# SCH_Manta_2023-12-03.net
KiCad netlist of a schematic drawn in EasyEDA
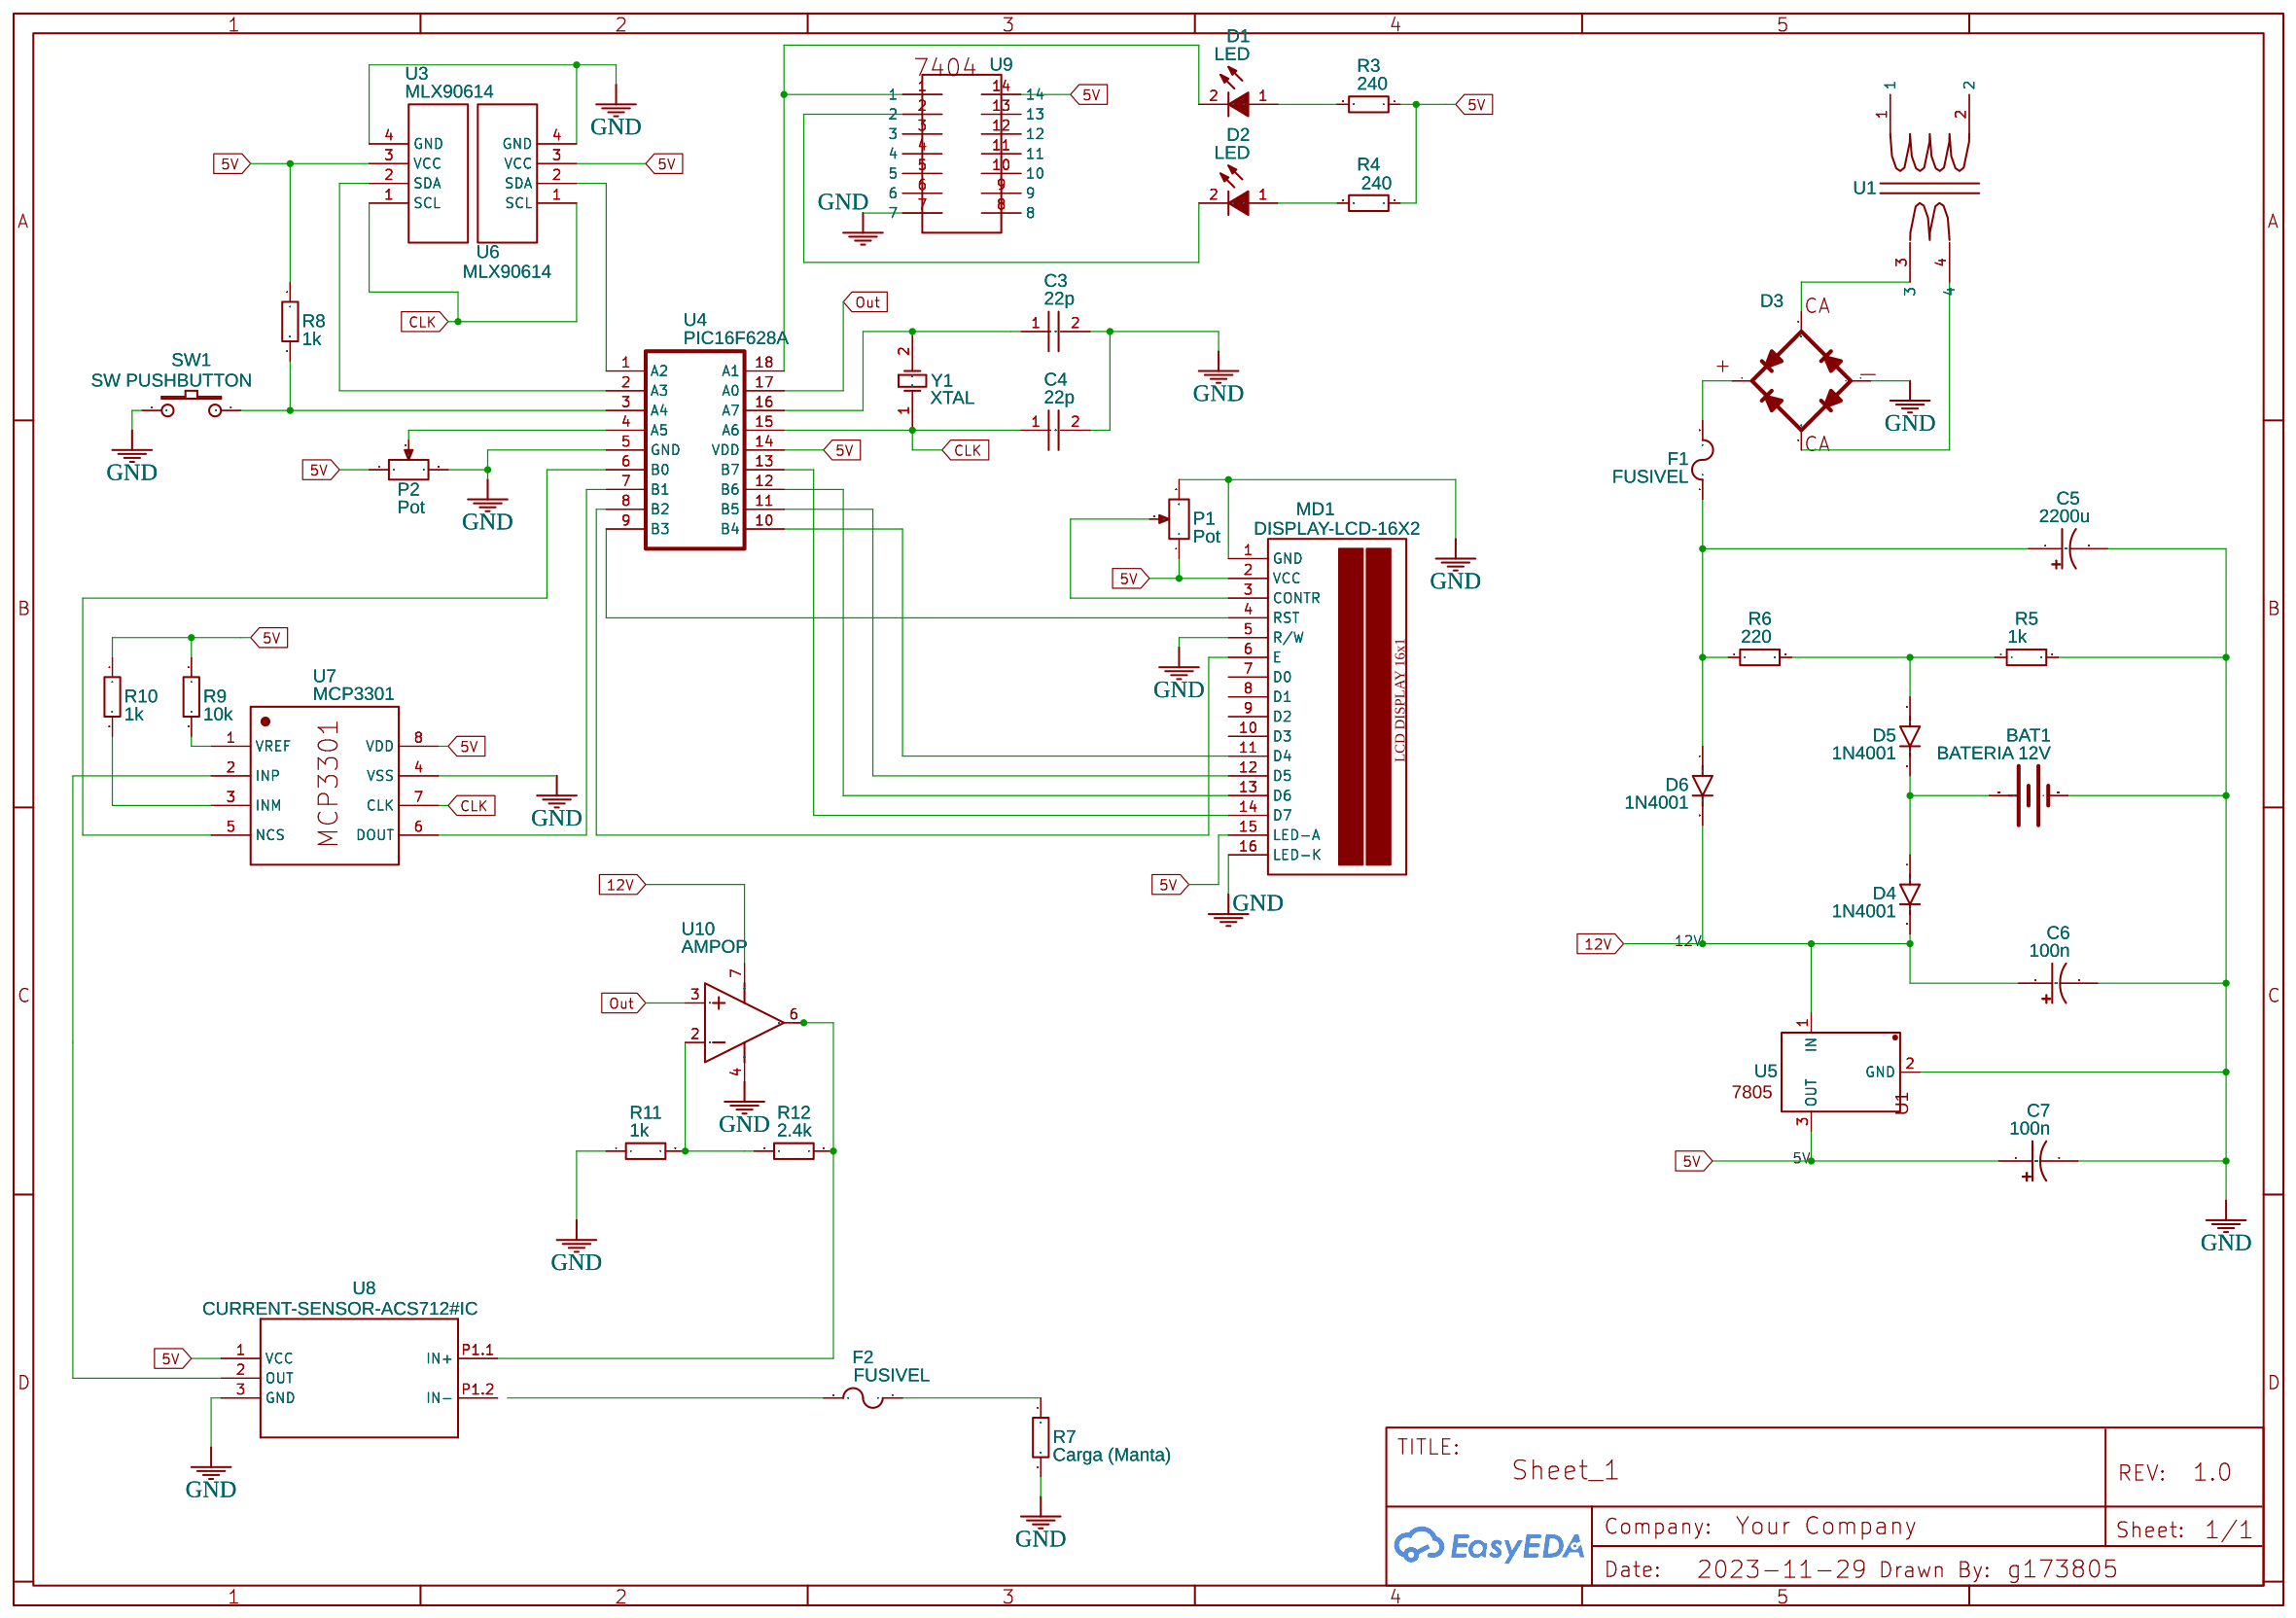
[diagram p0: Sheet_1]
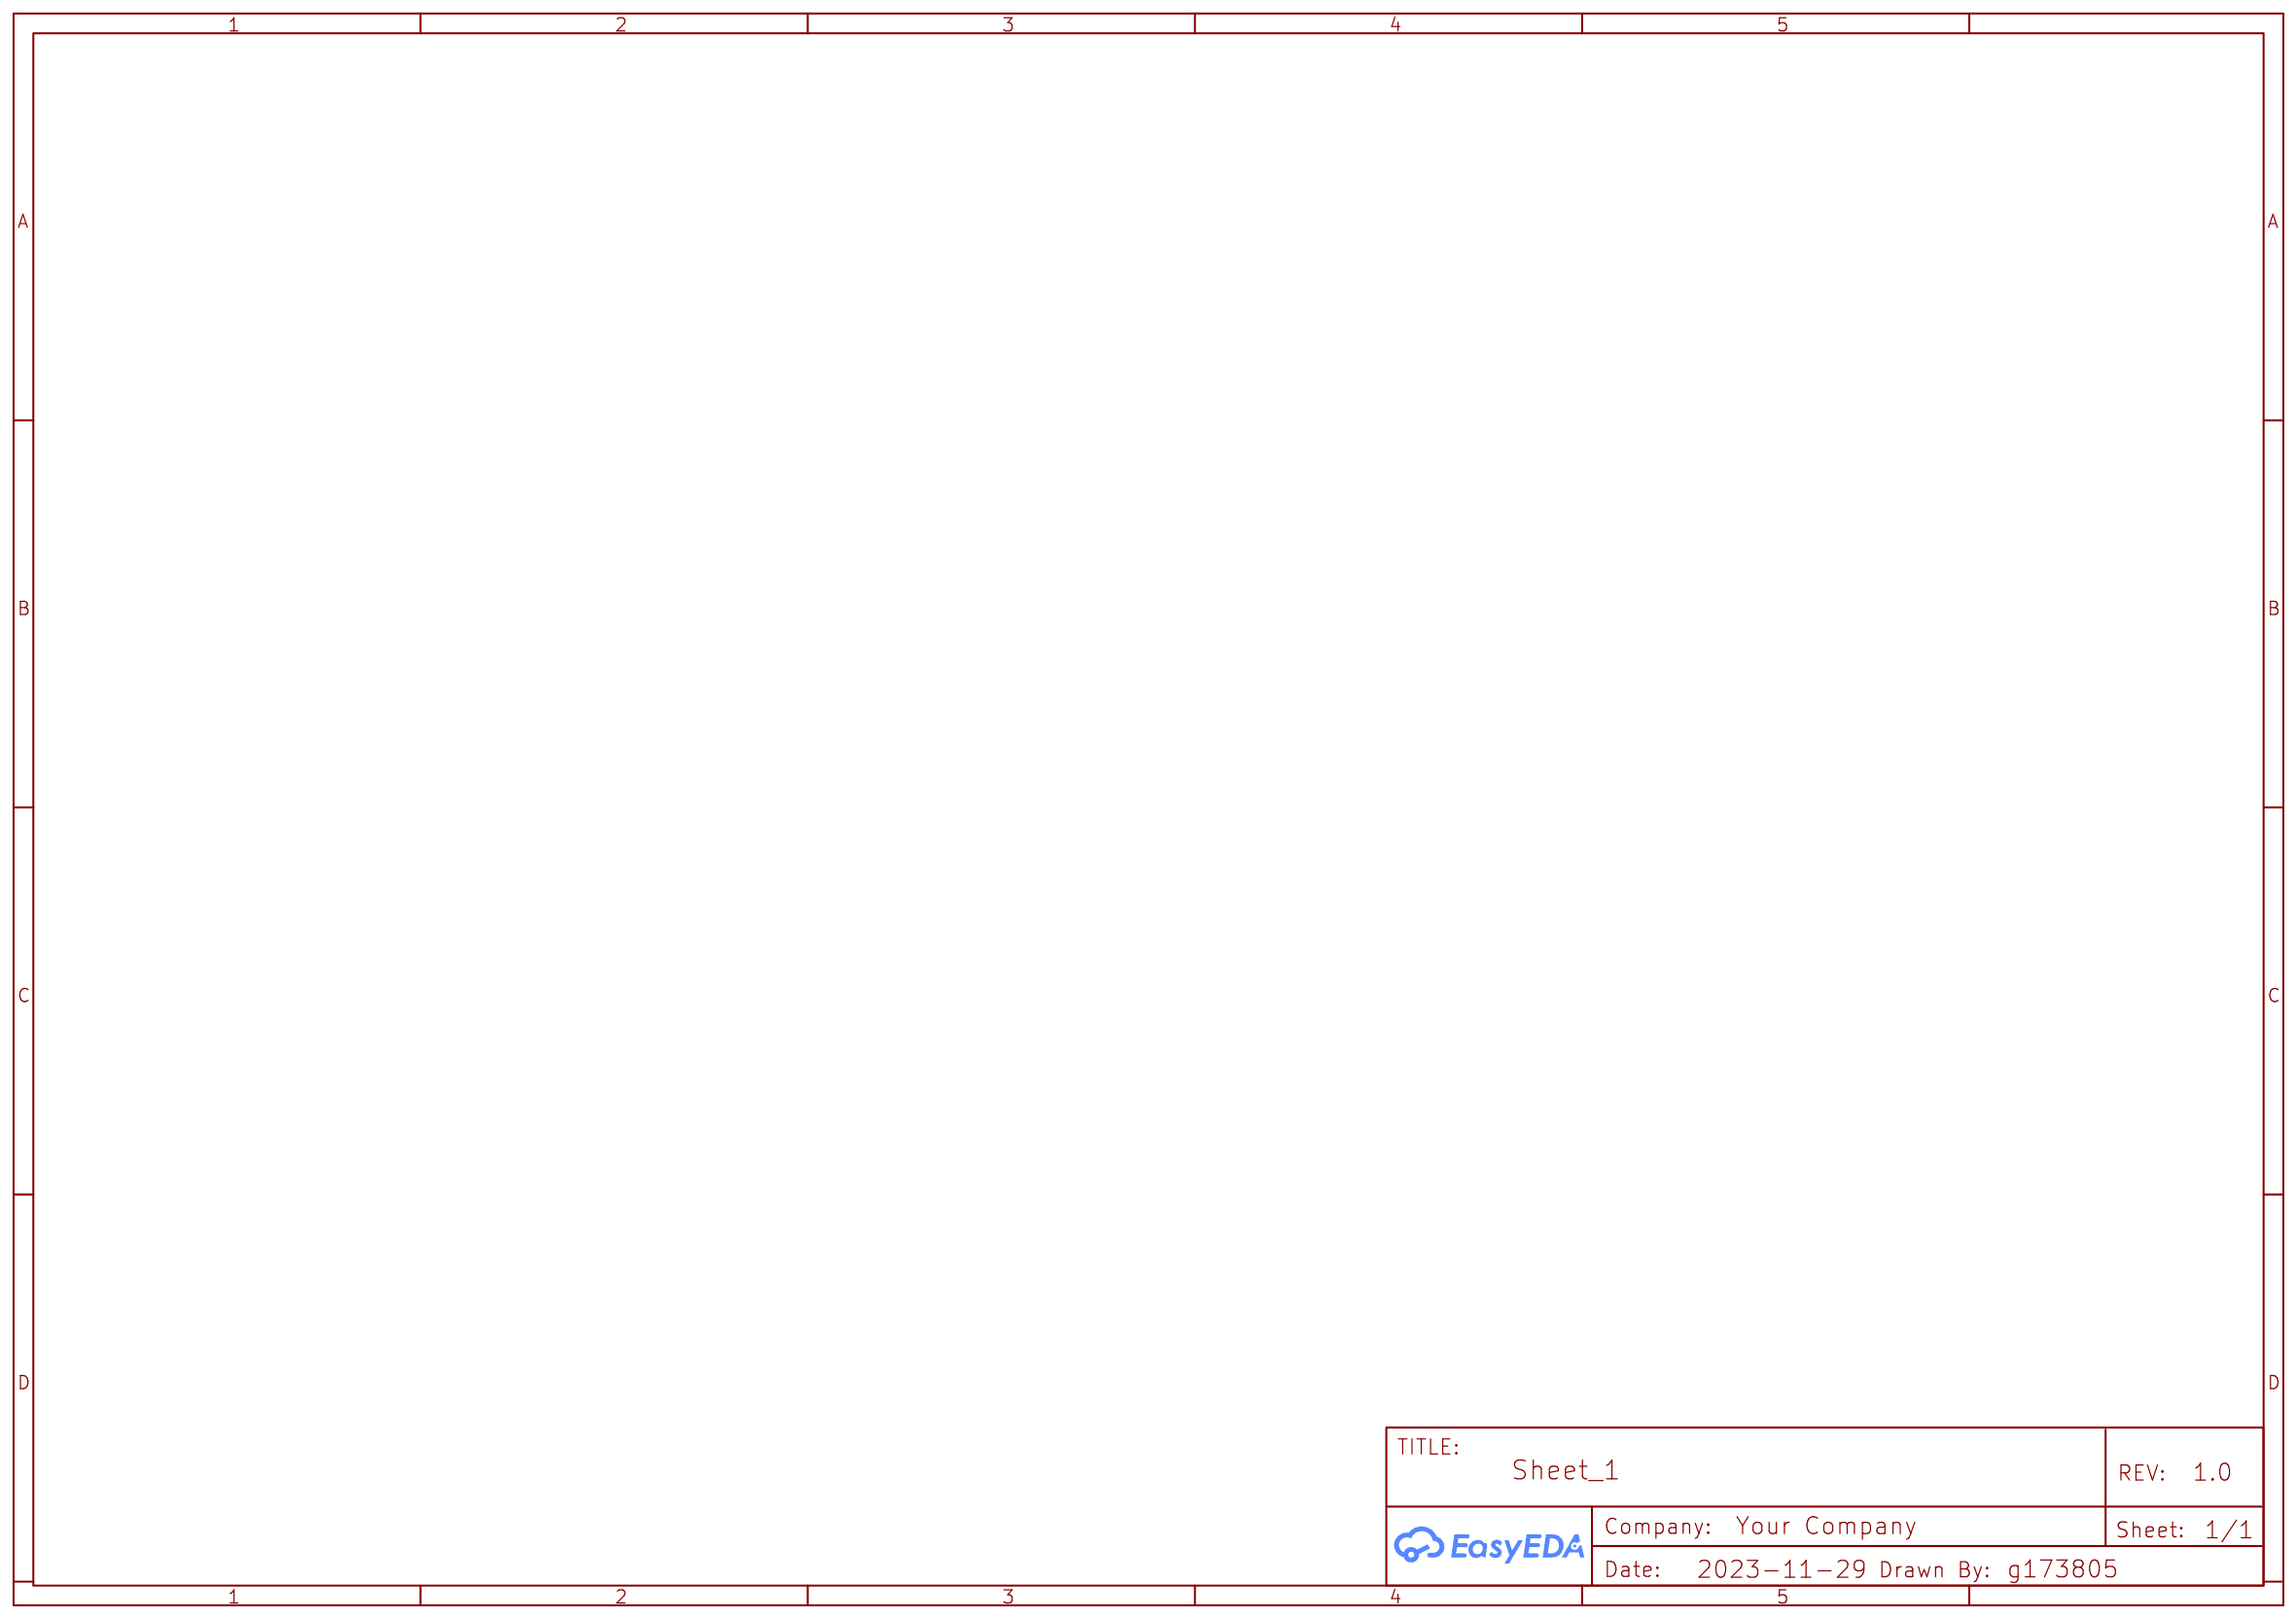
[diagram p1: Sheet_2]

(export (version "E")
  (design (tool "Eeschema 10.0.6"))
  (components
    (comp (ref "BAT1") (value "BATERIA 12V") (libsource (lib "") (part "BATERIA-AA-2")))
    (comp (ref "C3") (value "22p") (libsource (lib "") (part "100 UF CAPACIROR 400V")))
    (comp (ref "C4") (value "22p") (libsource (lib "") (part "100 UF CAPACIROR 400V")))
    (comp (ref "C5")
      (value "2200u")
      (fields
        (field (name "Manufacturer Part") "KM221M010E110A")
        (field (name "Manufacturer") "Capxon International Elec")
      )
      (libsource (lib "") (part "CAPACITOR"))
    )
    (comp (ref "C6")
      (value "100n")
      (fields
        (field (name "Manufacturer Part") "KM221M010E110A")
        (field (name "Manufacturer") "Capxon International Elec")
      )
      (libsource (lib "") (part "CAPACITOR"))
    )
    (comp (ref "C7")
      (value "100n")
      (fields
        (field (name "Manufacturer Part") "KM221M010E110A")
        (field (name "Manufacturer") "Capxon International Elec")
      )
      (libsource (lib "") (part "CAPACITOR_1"))
    )
    (comp (ref "D1")
      (value "LED")
      (fields (field (name "Manufacturer Part") "5600") (field (name "Manufacturer") "VccLite"))
      (libsource (lib "") (part "LED"))
    )
    (comp (ref "D2")
      (value "LED")
      (fields (field (name "Manufacturer Part") "5600") (field (name "Manufacturer") "VccLite"))
      (libsource (lib "") (part "LED"))
    )
    (comp (ref "D3") (value "PONTE RETIFICADORA") (libsource (lib "") (part "PONTE RETIFICADORA")))
    (comp (ref "D4")
      (value "1N4001")
      (fields (field (name "Manufacturer Part") "RD 1/4W 10K J T/B A1") (field (name "Manufacturer") "TyoHM"))
      (libsource (lib "") (part "Diodo 1N4001"))
    )
    (comp (ref "D5")
      (value "1N4001")
      (fields (field (name "Manufacturer Part") "RD 1/4W 10K J T/B A1") (field (name "Manufacturer") "TyoHM"))
      (libsource (lib "") (part "Diodo 1N4001"))
    )
    (comp (ref "D6")
      (value "1N4001")
      (fields (field (name "Manufacturer Part") "RD 1/4W 10K J T/B A1") (field (name "Manufacturer") "TyoHM"))
      (libsource (lib "") (part "Diodo 1N4001"))
    )
    (comp (ref "F1")
      (value "FUSIVEL")
      (fields
        (field (name "Manufacturer Part") "Glass tube fuse2A 3F 250VAC")
        (field (name "Manufacturer") "XCFuse")
      )
      (libsource (lib "") (part "FUSIVEL_1"))
    )
    (comp (ref "F2")
      (value "FUSIVEL")
      (fields
        (field (name "Manufacturer Part") "Glass tube fuse2A 3F 250VAC")
        (field (name "Manufacturer") "XCFuse")
      )
      (libsource (lib "") (part "FUSIVEL"))
    )
    (comp (ref "MD1") (value "DISPLAY-LCD-16X2") (libsource (lib "") (part "DISPLAY-LCD-16X2")))
    (comp (ref "P1") (value "Pot") (libsource (lib "") (part "Pot_blue")))
    (comp (ref "P2") (value "Pot") (libsource (lib "") (part "Pot_blue_1")))
    (comp (ref "R3")
      (value "240")
      (fields
        (field (name "Manufacturer Part") "EWWR0001J20R0T9")
        (field (name "Manufacturer") "ResistorToday")
      )
      (libsource (lib "") (part "Resistor Normal"))
    )
    (comp (ref "R4")
      (value "240")
      (fields
        (field (name "Manufacturer Part") "EWWR0001J20R0T9")
        (field (name "Manufacturer") "ResistorToday")
      )
      (libsource (lib "") (part "Resistor Normal"))
    )
    (comp (ref "R5")
      (value "1k")
      (fields
        (field (name "Manufacturer Part") "EWWR0001J20R0T9")
        (field (name "Manufacturer") "ResistorToday")
      )
      (libsource (lib "") (part "Resistor Normal_1"))
    )
    (comp (ref "R6")
      (value "220")
      (fields
        (field (name "Manufacturer Part") "EWWR0001J20R0T9")
        (field (name "Manufacturer") "ResistorToday")
      )
      (libsource (lib "") (part "Resistor Normal_1"))
    )
    (comp (ref "R7")
      (value "Carga (Manta)")
      (fields
        (field (name "Manufacturer Part") "EWSL3920FL200S9")
        (field (name "Manufacturer") "ResistorToday")
      )
      (libsource (lib "") (part "RESISTOR DE POTENCIA"))
    )
    (comp (ref "R8")
      (value "1k")
      (fields
        (field (name "Manufacturer Part") "EWSL3920FL200S9")
        (field (name "Manufacturer") "ResistorToday")
      )
      (libsource (lib "") (part "RESISTOR DE POTENCIA"))
    )
    (comp (ref "R9")
      (value "10k")
      (fields
        (field (name "Manufacturer Part") "EWSL3920FL200S9")
        (field (name "Manufacturer") "ResistorToday")
      )
      (libsource (lib "") (part "RESISTOR DE POTENCIA"))
    )
    (comp (ref "R10")
      (value "1k")
      (fields
        (field (name "Manufacturer Part") "EWSL3920FL200S9")
        (field (name "Manufacturer") "ResistorToday")
      )
      (libsource (lib "") (part "RESISTOR DE POTENCIA"))
    )
    (comp (ref "R11")
      (value "1k")
      (fields
        (field (name "Manufacturer Part") "EWSL3920FL200S9")
        (field (name "Manufacturer") "ResistorToday")
      )
      (libsource (lib "") (part "RESISTOR DE POTENCIA_1"))
    )
    (comp (ref "R12")
      (value "2.4k")
      (fields
        (field (name "Manufacturer Part") "EWSL3920FL200S9")
        (field (name "Manufacturer") "ResistorToday")
      )
      (libsource (lib "") (part "RESISTOR DE POTENCIA_1"))
    )
    (comp (ref "SW1") (value "SW PUSHBUTTON") (libsource (lib "") (part "SW PUSHBUTTON")))
    (comp (ref "U1") (value "simbolo transformador") (libsource (lib "") (part "simbolo transformador")))
    (comp (ref "U3")
      (value "MLX90614")
      (fields (field (name "Manufacturer") "Melexis"))
      (libsource (lib "") (part "MLX90614_th_1"))
    )
    (comp (ref "U4") (value "PIC16F628A") (libsource (lib "") (part "PIC16F628A")))
    (comp (ref "U5") (value "7805") (libsource (lib "") (part "7805")))
    (comp (ref "U6")
      (value "MLX90614")
      (fields (field (name "Manufacturer") "Melexis"))
      (libsource (lib "") (part "MLX90614_th"))
    )
    (comp (ref "U7") (value "MCP3301") (libsource (lib "") (part "MCP3301")))
    (comp (ref "U8")
      (value "CURRENT-SENSOR-ACS712#IC")
      (libsource (lib "") (part "CURRENT-SENSOR-ACS712#IC"))
    )
    (comp (ref "U9") (value "7404") (libsource (lib "") (part "7404")))
    (comp (ref "U10")
      (value "AMPOP")
      (fields (field (name "Manufacturer Part") "OP07CP") (field (name "Manufacturer") "TI"))
      (libsource (lib "") (part "AMPOP"))
    )
    (comp (ref "Y1") (value "XTAL") (libsource (lib "") (part "XTAL")))
  )
  (nets
    (net (code "1") (name "5V") (class "Default")
      (node (ref "C7") (pin "1") (pinfunction "1_1") (pintype "unspecified"))
      (node (ref "MD1") (pin "15") (pinfunction "LED-A_15") (pintype "unspecified"))
      (node (ref "MD1") (pin "2") (pinfunction "VCC_2") (pintype "unspecified"))
      (node (ref "P1") (pin "1") (pinfunction "1_1") (pintype "input"))
      (node (ref "P2") (pin "1") (pinfunction "1_1") (pintype "input"))
      (node (ref "R10") (pin "1") (pinfunction "1_1") (pintype "unspecified"))
      (node (ref "R3") (pin "1") (pinfunction "1_1") (pintype "unspecified"))
      (node (ref "R4") (pin "1") (pinfunction "1_1") (pintype "unspecified"))
      (node (ref "R8") (pin "1") (pinfunction "1_1") (pintype "unspecified"))
      (node (ref "R9") (pin "1") (pinfunction "1_1") (pintype "unspecified"))
      (node (ref "U3") (pin "3") (pinfunction "VCC_3") (pintype "unspecified"))
      (node (ref "U4") (pin "14") (pinfunction "VDD_14") (pintype "unspecified"))
      (node (ref "U5") (pin "3") (pinfunction "OUT_3") (pintype "unspecified"))
      (node (ref "U6") (pin "3") (pinfunction "VCC_3") (pintype "unspecified"))
      (node (ref "U7") (pin "8") (pinfunction "VDD_8") (pintype "unspecified"))
      (node (ref "U8") (pin "1") (pinfunction "VCC_1") (pintype "passive"))
      (node (ref "U9") (pin "14") (pinfunction "14_14") (pintype "unspecified"))
    )
    (net (code "2") (name "12V") (class "Default")
      (node (ref "C6") (pin "1") (pinfunction "1_1") (pintype "unspecified"))
      (node (ref "D4") (pin "2") (pinfunction "2_2") (pintype "unspecified"))
      (node (ref "D6") (pin "2") (pinfunction "2_2") (pintype "unspecified"))
      (node (ref "U10") (pin "7") (pinfunction "VCC+_7") (pintype "passive"))
      (node (ref "U5") (pin "1") (pinfunction "IN_1") (pintype "unspecified"))
    )
    (net (code "3") (name "CLK") (class "Default")
      (node (ref "C4") (pin "1") (pinfunction "1_1") (pintype "unspecified"))
      (node (ref "U3") (pin "1") (pinfunction "SCL_1") (pintype "unspecified"))
      (node (ref "U4") (pin "15") (pinfunction "A6_15") (pintype "unspecified"))
      (node (ref "U6") (pin "1") (pinfunction "SCL_1") (pintype "unspecified"))
      (node (ref "U7") (pin "7") (pinfunction "CLK_7") (pintype "unspecified"))
      (node (ref "Y1") (pin "1") (pinfunction "OSC1_1") (pintype "unspecified"))
    )
    (net (code "4") (name "GND") (class "Default")
      (node (ref "BAT1") (pin "GND@1") (pinfunction "-_GND@1") (pintype "passive"))
      (node (ref "C3") (pin "2") (pinfunction "2_2") (pintype "unspecified"))
      (node (ref "C4") (pin "2") (pinfunction "2_2") (pintype "unspecified"))
      (node (ref "C5") (pin "2") (pinfunction "2_2") (pintype "unspecified"))
      (node (ref "C6") (pin "2") (pinfunction "2_2") (pintype "unspecified"))
      (node (ref "C7") (pin "2") (pinfunction "2_2") (pintype "unspecified"))
      (node (ref "D3") (pin "|") (pinfunction "-_|") (pintype "input"))
      (node (ref "MD1") (pin "1") (pinfunction "GND_1") (pintype "unspecified"))
      (node (ref "MD1") (pin "16") (pinfunction "LED-K_16") (pintype "unspecified"))
      (node (ref "MD1") (pin "5") (pinfunction "R/W_5") (pintype "unspecified"))
      (node (ref "P1") (pin "3") (pinfunction "2_3") (pintype "input"))
      (node (ref "P2") (pin "3") (pinfunction "2_3") (pintype "input"))
      (node (ref "R11") (pin "1") (pinfunction "1_1") (pintype "unspecified"))
      (node (ref "R5") (pin "2") (pinfunction "2_2") (pintype "unspecified"))
      (node (ref "R7") (pin "2") (pinfunction "2_2") (pintype "unspecified"))
      (node (ref "SW1") (pin "1") (pinfunction "1_1") (pintype "unspecified"))
      (node (ref "U10") (pin "4") (pinfunction "VCC-_4") (pintype "passive"))
      (node (ref "U3") (pin "4") (pinfunction "GND_4") (pintype "unspecified"))
      (node (ref "U4") (pin "5") (pinfunction "GND_5") (pintype "unspecified"))
      (node (ref "U5") (pin "2") (pinfunction "GND_2") (pintype "unspecified"))
      (node (ref "U6") (pin "4") (pinfunction "GND_4") (pintype "unspecified"))
      (node (ref "U7") (pin "4") (pinfunction "VSS_4") (pintype "unspecified"))
      (node (ref "U8") (pin "3") (pinfunction "GND_3") (pintype "passive"))
      (node (ref "U9") (pin "7") (pinfunction "7_7") (pintype "unspecified"))
    )
    (net (code "5") (name "Net-(BAT1-+)") (class "Default")
      (node (ref "BAT1") (pin "PWR@1") (pinfunction "+_PWR@1") (pintype "passive"))
      (node (ref "D4") (pin "1") (pinfunction "1_1") (pintype "unspecified"))
      (node (ref "D5") (pin "2") (pinfunction "2_2") (pintype "unspecified"))
    )
    (net (code "6") (name "Net-(C5-Pad1)") (class "Default")
      (node (ref "C5") (pin "1") (pinfunction "1_1") (pintype "unspecified"))
      (node (ref "D6") (pin "1") (pinfunction "1_1") (pintype "unspecified"))
      (node (ref "F1") (pin "1") (pinfunction "1_1") (pintype "unspecified"))
      (node (ref "R6") (pin "1") (pinfunction "1_1") (pintype "unspecified"))
    )
    (net (code "7") (name "Net-(D1-A)") (class "Default")
      (node (ref "D1") (pin "1") (pinfunction "A_1") (pintype "unspecified"))
      (node (ref "R3") (pin "2") (pinfunction "2_2") (pintype "unspecified"))
    )
    (net (code "8") (name "Net-(D1-K)") (class "Default")
      (node (ref "D1") (pin "2") (pinfunction "K_2") (pintype "unspecified"))
      (node (ref "U4") (pin "18") (pinfunction "A1_18") (pintype "unspecified"))
      (node (ref "U9") (pin "1") (pinfunction "1_1") (pintype "unspecified"))
    )
    (net (code "9") (name "Net-(D2-A)") (class "Default")
      (node (ref "D2") (pin "1") (pinfunction "A_1") (pintype "unspecified"))
      (node (ref "R4") (pin "2") (pinfunction "2_2") (pintype "unspecified"))
    )
    (net (code "10") (name "Net-(D2-K)") (class "Default")
      (node (ref "D2") (pin "2") (pinfunction "K_2") (pintype "unspecified"))
      (node (ref "U9") (pin "2") (pinfunction "2_2") (pintype "unspecified"))
    )
    (net (code "11") (name "Net-(D3-Pad+)") (class "Default")
      (node (ref "D3") (pin "+") (pintype "input"))
      (node (ref "F1") (pin "2") (pinfunction "2_2") (pintype "unspecified"))
    )
    (net (code "12") (name "Net-(D5-Pad1)") (class "Default")
      (node (ref "D5") (pin "1") (pinfunction "1_1") (pintype "unspecified"))
      (node (ref "R5") (pin "1") (pinfunction "1_1") (pintype "unspecified"))
      (node (ref "R6") (pin "2") (pinfunction "2_2") (pintype "unspecified"))
    )
    (net (code "13") (name "Net-(F2-Pad1)") (class "Default")
      (node (ref "F2") (pin "1") (pinfunction "1_1") (pintype "unspecified"))
      (node (ref "R7") (pin "1") (pinfunction "1_1") (pintype "unspecified"))
    )
    (net (code "14") (name "Net-(MD1-CONTR)") (class "Default")
      (node (ref "MD1") (pin "3") (pinfunction "CONTR_3") (pintype "unspecified"))
      (node (ref "P1") (pin "2") (pinfunction "3_2") (pintype "input"))
    )
    (net (code "15") (name "Net-(MD1-D4)") (class "Default")
      (node (ref "MD1") (pin "11") (pinfunction "D4_11") (pintype "unspecified"))
      (node (ref "U4") (pin "10") (pinfunction "B4_10") (pintype "unspecified"))
    )
    (net (code "16") (name "Net-(MD1-D5)") (class "Default")
      (node (ref "MD1") (pin "12") (pinfunction "D5_12") (pintype "unspecified"))
      (node (ref "U4") (pin "11") (pinfunction "B5_11") (pintype "unspecified"))
    )
    (net (code "17") (name "Net-(MD1-D6)") (class "Default")
      (node (ref "MD1") (pin "13") (pinfunction "D6_13") (pintype "unspecified"))
      (node (ref "U4") (pin "12") (pinfunction "B6_12") (pintype "unspecified"))
    )
    (net (code "18") (name "Net-(MD1-D7)") (class "Default")
      (node (ref "MD1") (pin "14") (pinfunction "D7_14") (pintype "unspecified"))
      (node (ref "U4") (pin "13") (pinfunction "B7_13") (pintype "unspecified"))
    )
    (net (code "19") (name "Net-(MD1-E)") (class "Default")
      (node (ref "MD1") (pin "6") (pinfunction "E_6") (pintype "unspecified"))
      (node (ref "U4") (pin "8") (pinfunction "B2_8") (pintype "unspecified"))
    )
    (net (code "20") (name "Net-(MD1-RST)") (class "Default")
      (node (ref "MD1") (pin "4") (pinfunction "RST_4") (pintype "unspecified"))
      (node (ref "U4") (pin "9") (pinfunction "B3_9") (pintype "unspecified"))
    )
    (net (code "21") (name "Net-(P2-3)") (class "Default")
      (node (ref "P2") (pin "2") (pinfunction "3_2") (pintype "input"))
      (node (ref "U4") (pin "4") (pinfunction "A5_4") (pintype "unspecified"))
    )
    (net (code "22") (name "Net-(U3-SDA)") (class "Default")
      (node (ref "U3") (pin "2") (pinfunction "SDA_2") (pintype "unspecified"))
      (node (ref "U4") (pin "2") (pinfunction "A3_2") (pintype "unspecified"))
    )
    (net (code "23") (name "Net-(U4-A2)") (class "Default")
      (node (ref "U4") (pin "1") (pinfunction "A2_1") (pintype "unspecified"))
      (node (ref "U6") (pin "2") (pinfunction "SDA_2") (pintype "unspecified"))
    )
    (net (code "24") (name "Net-(U4-A4)") (class "Default")
      (node (ref "R8") (pin "2") (pinfunction "2_2") (pintype "unspecified"))
      (node (ref "SW1") (pin "2") (pinfunction "2_2") (pintype "unspecified"))
      (node (ref "U4") (pin "3") (pinfunction "A4_3") (pintype "unspecified"))
    )
    (net (code "25") (name "Net-(U4-A7)") (class "Default")
      (node (ref "C3") (pin "1") (pinfunction "1_1") (pintype "unspecified"))
      (node (ref "U4") (pin "16") (pinfunction "A7_16") (pintype "unspecified"))
      (node (ref "Y1") (pin "2") (pinfunction "OSC2_2") (pintype "unspecified"))
    )
    (net (code "26") (name "Net-(U4-B0)") (class "Default")
      (node (ref "U4") (pin "6") (pinfunction "B0_6") (pintype "unspecified"))
      (node (ref "U7") (pin "5") (pinfunction "NCS_5") (pintype "unspecified"))
    )
    (net (code "27") (name "Net-(U4-B1)") (class "Default")
      (node (ref "U4") (pin "7") (pinfunction "B1_7") (pintype "unspecified"))
      (node (ref "U7") (pin "6") (pinfunction "DOUT_6") (pintype "unspecified"))
    )
    (net (code "28") (name "Net-(U7-INM)") (class "Default")
      (node (ref "R10") (pin "2") (pinfunction "2_2") (pintype "unspecified"))
      (node (ref "U7") (pin "3") (pinfunction "INM_3") (pintype "unspecified"))
    )
    (net (code "29") (name "Net-(U7-INP)") (class "Default")
      (node (ref "U7") (pin "2") (pinfunction "INP_2") (pintype "unspecified"))
      (node (ref "U8") (pin "2") (pinfunction "OUT_2") (pintype "output"))
    )
    (net (code "30") (name "Net-(U7-VREF)") (class "Default")
      (node (ref "R9") (pin "2") (pinfunction "2_2") (pintype "unspecified"))
      (node (ref "U7") (pin "1") (pinfunction "VREF_1") (pintype "unspecified"))
    )
    (net (code "31") (name "Net-(U10-IN-)") (class "Default")
      (node (ref "R11") (pin "2") (pinfunction "2_2") (pintype "unspecified"))
      (node (ref "R12") (pin "1") (pinfunction "1_1") (pintype "unspecified"))
      (node (ref "U10") (pin "2") (pinfunction "IN-_2") (pintype "unspecified"))
    )
    (net (code "32") (name "Net-(U10-OUT)") (class "Default")
      (node (ref "R12") (pin "2") (pinfunction "2_2") (pintype "unspecified"))
      (node (ref "U10") (pin "6") (pinfunction "OUT_6") (pintype "output"))
      (node (ref "U8") (pin "P1.1") (pinfunction "IN+_P1.1") (pintype "unspecified"))
    )
    (net (code "33") (name "Out") (class "Default")
      (node (ref "U10") (pin "3") (pinfunction "IN+_3") (pintype "unspecified"))
      (node (ref "U4") (pin "17") (pinfunction "A0_17") (pintype "unspecified"))
    )
    (net (code "34") (name "unconnected-(D3-CA-Pad1)") (class "Default")
      (node (ref "D3") (pin "1") (pinfunction "CA_1") (pintype "input"))
    )
    (net (code "35") (name "unconnected-(D3-CA-Pad2)") (class "Default")
      (node (ref "D3") (pin "2") (pinfunction "CA_2") (pintype "input"))
    )
    (net (code "36") (name "unconnected-(F2-Pad2)") (class "Default")
      (node (ref "F2") (pin "2") (pinfunction "2_2") (pintype "unspecified"))
    )
    (net (code "37") (name "unconnected-(MD1-D0-Pad7)") (class "Default")
      (node (ref "MD1") (pin "7") (pinfunction "D0_7") (pintype "unspecified"))
    )
    (net (code "38") (name "unconnected-(MD1-D1-Pad8)") (class "Default")
      (node (ref "MD1") (pin "8") (pinfunction "D1_8") (pintype "unspecified"))
    )
    (net (code "39") (name "unconnected-(MD1-D2-Pad9)") (class "Default")
      (node (ref "MD1") (pin "9") (pinfunction "D2_9") (pintype "unspecified"))
    )
    (net (code "40") (name "unconnected-(MD1-D3-Pad10)") (class "Default")
      (node (ref "MD1") (pin "10") (pinfunction "D3_10") (pintype "unspecified"))
    )
    (net (code "41") (name "unconnected-(U1-Pad1)") (class "Default")
      (node (ref "U1") (pin "1") (pinfunction "1_1") (pintype "unspecified"))
    )
    (net (code "42") (name "unconnected-(U1-Pad2)") (class "Default")
      (node (ref "U1") (pin "2") (pinfunction "2_2") (pintype "unspecified"))
    )
    (net (code "43") (name "unconnected-(U1-Pad3)") (class "Default")
      (node (ref "U1") (pin "3") (pinfunction "3_3") (pintype "unspecified"))
    )
    (net (code "44") (name "unconnected-(U1-Pad4)") (class "Default")
      (node (ref "U1") (pin "4") (pinfunction "4_4") (pintype "unspecified"))
    )
    (net (code "45") (name "unconnected-(U8-IN--PadP1.2)") (class "Default")
      (node (ref "U8") (pin "P1.2") (pinfunction "IN-_P1.2") (pintype "unspecified"))
    )
    (net (code "46") (name "unconnected-(U9-Pad3)") (class "Default")
      (node (ref "U9") (pin "3") (pinfunction "3_3") (pintype "unspecified"))
    )
    (net (code "47") (name "unconnected-(U9-Pad4)") (class "Default")
      (node (ref "U9") (pin "4") (pinfunction "4_4") (pintype "unspecified"))
    )
    (net (code "48") (name "unconnected-(U9-Pad5)") (class "Default")
      (node (ref "U9") (pin "5") (pinfunction "5_5") (pintype "unspecified"))
    )
    (net (code "49") (name "unconnected-(U9-Pad6)") (class "Default")
      (node (ref "U9") (pin "6") (pinfunction "6_6") (pintype "unspecified"))
    )
    (net (code "50") (name "unconnected-(U9-Pad8)") (class "Default")
      (node (ref "U9") (pin "8") (pinfunction "8_8") (pintype "unspecified"))
    )
    (net (code "51") (name "unconnected-(U9-Pad9)") (class "Default")
      (node (ref "U9") (pin "9") (pinfunction "9_9") (pintype "unspecified"))
    )
    (net (code "52") (name "unconnected-(U9-Pad10)") (class "Default")
      (node (ref "U9") (pin "10") (pinfunction "10_10") (pintype "unspecified"))
    )
    (net (code "53") (name "unconnected-(U9-Pad11)") (class "Default")
      (node (ref "U9") (pin "11") (pinfunction "11_11") (pintype "unspecified"))
    )
    (net (code "54") (name "unconnected-(U9-Pad12)") (class "Default")
      (node (ref "U9") (pin "12") (pinfunction "12_12") (pintype "unspecified"))
    )
    (net (code "55") (name "unconnected-(U9-Pad13)") (class "Default")
      (node (ref "U9") (pin "13") (pinfunction "13_13") (pintype "unspecified"))
    )
  )
)
